# Sheet1.net
KiCad netlist of a schematic drawn in Altium Designer
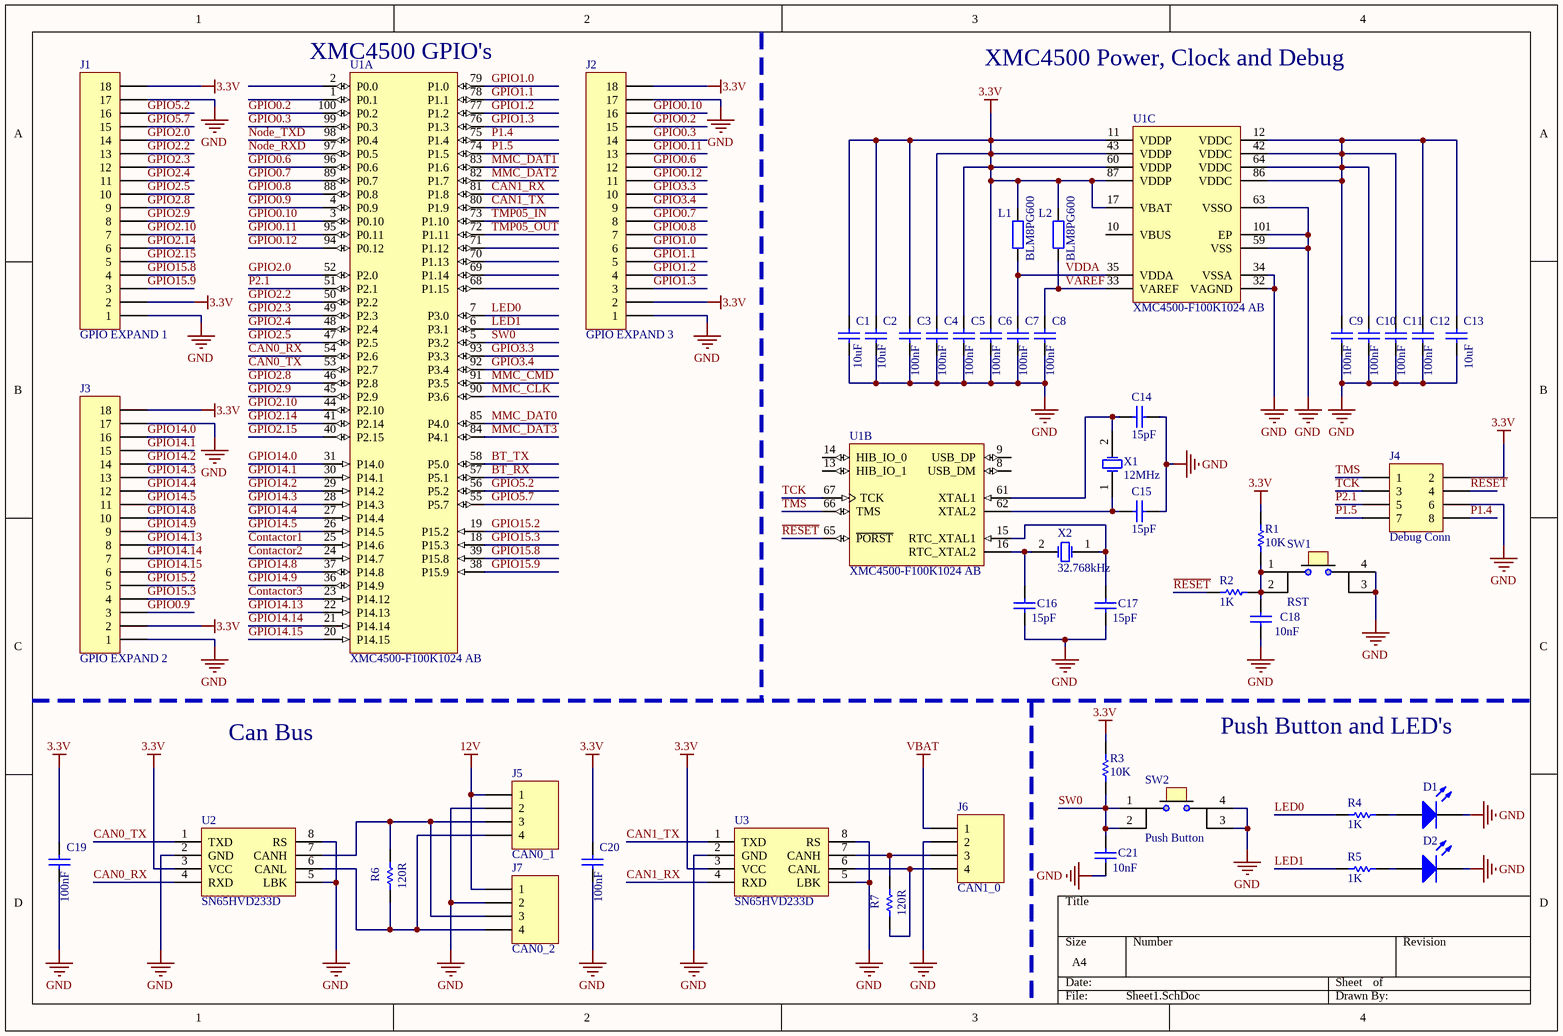
[diagram p0: Sheet1.SchDoc]

(export (version "E")
  (design (tool "Eeschema 10.0.6"))
  (components
    (comp (ref "C1")
      (value "10uF")
      (footprint "C0805")
      (fields (field (name "PUBLISHER") "Altium Limited"))
      (libsource (lib "Miscellaneous Devices") (part "Cap Semi"))
    )
    (comp (ref "C2")
      (value "10uF")
      (footprint "C0805")
      (fields (field (name "PUBLISHER") "Altium Limited"))
      (libsource (lib "Miscellaneous Devices") (part "Cap Semi"))
    )
    (comp (ref "C3")
      (value "100nF")
      (footprint "1608[0603]")
      (fields (field (name "PUBLISHER") "Altium Limited"))
      (libsource (lib "Miscellaneous Devices") (part "Cap Semi"))
    )
    (comp (ref "C4")
      (value "100nF")
      (footprint "1608[0603]")
      (fields (field (name "PUBLISHER") "Altium Limited"))
      (libsource (lib "Miscellaneous Devices") (part "Cap Semi"))
    )
    (comp (ref "C5")
      (value "100nF")
      (footprint "1608[0603]")
      (fields (field (name "PUBLISHER") "Altium Limited"))
      (libsource (lib "Miscellaneous Devices") (part "Cap Semi"))
    )
    (comp (ref "C6")
      (value "100nF")
      (footprint "1608[0603]")
      (fields (field (name "PUBLISHER") "Altium Limited"))
      (libsource (lib "Miscellaneous Devices") (part "Cap Semi"))
    )
    (comp (ref "C7")
      (value "100nF")
      (footprint "1608[0603]")
      (fields (field (name "PUBLISHER") "Altium Limited"))
      (libsource (lib "Miscellaneous Devices") (part "Cap Semi"))
    )
    (comp (ref "C8")
      (value "100nF")
      (footprint "1608[0603]")
      (fields (field (name "PUBLISHER") "Altium Limited"))
      (libsource (lib "Miscellaneous Devices") (part "Cap Semi"))
    )
    (comp (ref "C9")
      (value "100nF")
      (footprint "1608[0603]")
      (fields (field (name "PUBLISHER") "Altium Limited"))
      (libsource (lib "Miscellaneous Devices") (part "Cap Semi"))
    )
    (comp (ref "C10")
      (value "100nF")
      (footprint "1608[0603]")
      (fields (field (name "PUBLISHER") "Altium Limited"))
      (libsource (lib "Miscellaneous Devices") (part "Cap Semi"))
    )
    (comp (ref "C11")
      (value "100nF")
      (footprint "1608[0603]")
      (fields (field (name "PUBLISHER") "Altium Limited"))
      (libsource (lib "Miscellaneous Devices") (part "Cap Semi"))
    )
    (comp (ref "C12")
      (value "100nF")
      (footprint "1608[0603]")
      (fields (field (name "PUBLISHER") "Altium Limited"))
      (libsource (lib "Miscellaneous Devices") (part "Cap Semi"))
    )
    (comp (ref "C13")
      (value "10uF")
      (footprint "C0805")
      (fields (field (name "PUBLISHER") "Altium Limited"))
      (libsource (lib "Miscellaneous Devices") (part "Cap Semi"))
    )
    (comp (ref "C14")
      (value "15pF")
      (footprint "1608[0603]")
      (fields (field (name "PUBLISHER") "Altium Limited"))
      (libsource (lib "Miscellaneous Devices") (part "Cap Semi"))
    )
    (comp (ref "C15")
      (value "15pF")
      (footprint "1608[0603]")
      (fields (field (name "PUBLISHER") "Altium Limited"))
      (libsource (lib "Miscellaneous Devices") (part "Cap Semi"))
    )
    (comp (ref "C16")
      (value "15pF")
      (footprint "1608[0603]")
      (fields (field (name "PUBLISHER") "Altium Limited"))
      (libsource (lib "Miscellaneous Devices") (part "Cap Semi"))
    )
    (comp (ref "C17")
      (value "15pF")
      (footprint "1608[0603]")
      (fields (field (name "PUBLISHER") "Altium Limited"))
      (libsource (lib "Miscellaneous Devices") (part "Cap Semi"))
    )
    (comp (ref "C18")
      (value "10nF")
      (footprint "1608[0603]")
      (fields (field (name "PUBLISHER") "Altium Limited"))
      (libsource (lib "Miscellaneous Devices") (part "Cap Semi"))
    )
    (comp (ref "C19")
      (value "100nF")
      (footprint "1608[0603]")
      (fields (field (name "PUBLISHER") "Altium Limited"))
      (libsource (lib "Miscellaneous Devices") (part "Cap Semi"))
    )
    (comp (ref "C20")
      (value "100nF")
      (footprint "1608[0603]")
      (fields (field (name "PUBLISHER") "Altium Limited"))
      (libsource (lib "Miscellaneous Devices") (part "Cap Semi"))
    )
    (comp (ref "C21")
      (value "10nF")
      (footprint "1608[0603]")
      (fields (field (name "PUBLISHER") "Altium Limited"))
      (libsource (lib "Miscellaneous Devices") (part "Cap Semi"))
    )
    (comp (ref "D1")
      (value "SMD LED")
      (footprint "C0805")
      (fields (field (name "PUBLISHER") "Altium Limited"))
      (libsource (lib "Miscellaneous Devices") (part "LED0"))
    )
    (comp (ref "D2")
      (value "SMD LED")
      (footprint "C0805")
      (fields (field (name "PUBLISHER") "Altium Limited"))
      (libsource (lib "Miscellaneous Devices") (part "LED0"))
    )
    (comp (ref "J1")
      (value "GPIO EXPAND 1")
      (footprint "HDR1X18")
      (description "Header, 18-Pin")
      (fields (field (name "PUBLISHER") "Altium Limited"))
      (libsource (lib "Miscellaneous Connectors") (part "MHDR1X18"))
    )
    (comp (ref "J2")
      (value "GPIO EXPAND 3")
      (footprint "HDR1X18")
      (description "Header, 18-Pin")
      (fields (field (name "PUBLISHER") "Altium Limited"))
      (libsource (lib "Miscellaneous Connectors") (part "MHDR1X18"))
    )
    (comp (ref "J3")
      (value "GPIO EXPAND 2")
      (footprint "HDR1X18")
      (description "Header, 18-Pin")
      (fields (field (name "PUBLISHER") "Altium Limited"))
      (libsource (lib "Miscellaneous Connectors") (part "MHDR1X18"))
    )
    (comp (ref "J4")
      (value "Debug Conn")
      (footprint "HDR2X4")
      (description "Header, 4-Pin, Dual row")
      (fields (field (name "PUBLISHER") "Altium Limited"))
      (libsource (lib "Miscellaneous Connectors") (part "MHDR2X4"))
    )
    (comp (ref "J5")
      (value "CAN0_1")
      (footprint "4 Pin header")
      (description "4 pin header for CAN bus connectors")
      (libsource (lib "BMS") (part "4 Pin Vertical Header"))
    )
    (comp (ref "J6")
      (value "CAN1_0")
      (footprint "4 Pin header")
      (description "4 pin header for CAN bus connectors")
      (libsource (lib "BMS") (part "4 Pin Vertical Header"))
    )
    (comp (ref "J7")
      (value "CAN0_2")
      (footprint "4 Pin header")
      (description "4 pin header for CAN bus connectors")
      (libsource (lib "BMS") (part "4 Pin Vertical Header"))
    )
    (comp (ref "L1")
      (value "BLM8PG600")
      (footprint "C0805")
      (fields (field (name "PUBLISHER") "Altium Limited"))
      (libsource (lib "Miscellaneous Devices") (part "Res2"))
    )
    (comp (ref "L2")
      (value "BLM8PG600")
      (footprint "C0805")
      (fields (field (name "PUBLISHER") "Altium Limited"))
      (libsource (lib "Miscellaneous Devices") (part "Res2"))
    )
    (comp (ref "R1")
      (value "10K")
      (footprint "1608[0603]")
      (fields (field (name "PUBLISHER") "Altium Limited"))
      (libsource (lib "Miscellaneous Devices") (part "Res1"))
    )
    (comp (ref "R2")
      (value "1K")
      (footprint "1608[0603]")
      (description "10K")
      (fields (field (name "PUBLISHER") "Altium Limited"))
      (libsource (lib "Miscellaneous Devices") (part "Res1"))
    )
    (comp (ref "R3")
      (value "10K")
      (footprint "1608[0603]")
      (fields (field (name "PUBLISHER") "Altium Limited"))
      (libsource (lib "Miscellaneous Devices") (part "Res1"))
    )
    (comp (ref "R4")
      (value "1K")
      (footprint "1608[0603]")
      (fields (field (name "PUBLISHER") "Altium Limited"))
      (libsource (lib "Miscellaneous Devices") (part "Res1"))
    )
    (comp (ref "R5")
      (value "1K")
      (footprint "1608[0603]")
      (fields (field (name "PUBLISHER") "Altium Limited"))
      (libsource (lib "Miscellaneous Devices") (part "Res1"))
    )
    (comp (ref "R6")
      (value "120R")
      (footprint "C0805")
      (fields (field (name "PUBLISHER") "Altium Limited"))
      (libsource (lib "Miscellaneous Devices") (part "Res1"))
    )
    (comp (ref "R7")
      (value "120R")
      (footprint "C0805")
      (fields (field (name "PUBLISHER") "Altium Limited"))
      (libsource (lib "Miscellaneous Devices") (part "Res1"))
    )
    (comp (ref "SW1")
      (value "RST")
      (footprint "Push Button SMD")
      (description "General purposes push button")
      (libsource (lib "BMS") (part "Push Button"))
    )
    (comp (ref "SW2")
      (value "Push Button")
      (footprint "Push Button SMD")
      (description "General purposes push button")
      (libsource (lib "BMS") (part "Push Button"))
    )
    (comp (ref "U1")
      (value "XMC4500-F100K1024 AB")
      (footprint "INF-PG-LQFP-100-11-7000X7000TP_N")
      (fields (field (name "MANUFACTURER") "Infineon"))
      (libsource (lib "Infineon XMC4000") (part "XMC4500-F100K1024 AB"))
    )
    (comp (ref "U2")
      (value "SN65HVD233D")
      (footprint "SOIC 8")
      (description "SN65HVD233D 3.3V Can Tranceiver")
      (libsource (lib "BMS") (part "SN65HVD233D"))
    )
    (comp (ref "U3")
      (value "SN65HVD233D")
      (footprint "SOIC 8")
      (description "SN65HVD233D 3.3V Can Tranceiver")
      (libsource (lib "BMS") (part "SN65HVD233D"))
    )
    (comp (ref "X1")
      (value "12MHz")
      (footprint "SMD Crystall 23.2x2.5mm")
      (description "General purposes crystall symbol")
      (libsource (lib "BMS") (part "Crystall"))
    )
    (comp (ref "X2")
      (value "32.768kHz")
      (footprint "32kHz smd Crystal")
      (description "General purposes crystall symbol")
      (libsource (lib "BMS") (part "Crystall"))
    )
  )
  (nets
    (net (code "1") (name "/BT_RX") (class "Default")
      (node (ref "U1") (pin "57") (pinfunction "P5.1_57") (pintype "bidirectional"))
    )
    (net (code "2") (name "/BT_TX") (class "Default")
      (node (ref "U1") (pin "58") (pinfunction "P5.0_58") (pintype "bidirectional"))
    )
    (net (code "3") (name "/CAN0_RX") (class "Default")
      (node (ref "U1") (pin "54") (pinfunction "P2.6_54") (pintype "bidirectional"))
      (node (ref "U2") (pin "4") (pinfunction "RXD_4") (pintype "passive"))
    )
    (net (code "4") (name "/CAN0_TX") (class "Default")
      (node (ref "U1") (pin "53") (pinfunction "P2.7_53") (pintype "bidirectional"))
      (node (ref "U2") (pin "1") (pinfunction "TXD_1") (pintype "passive"))
    )
    (net (code "5") (name "/CAN1_RX") (class "Default")
      (node (ref "U1") (pin "81") (pinfunction "P1.8_81") (pintype "bidirectional"))
      (node (ref "U3") (pin "4") (pinfunction "RXD_4") (pintype "passive"))
    )
    (net (code "6") (name "/CAN1_TX") (class "Default")
      (node (ref "U1") (pin "80") (pinfunction "P1.9_80") (pintype "bidirectional"))
      (node (ref "U3") (pin "1") (pinfunction "TXD_1") (pintype "passive"))
    )
    (net (code "7") (name "/Contactor1") (class "Default")
      (node (ref "U1") (pin "25") (pinfunction "P14.6_25") (pintype "input"))
    )
    (net (code "8") (name "/Contactor2") (class "Default")
      (node (ref "U1") (pin "24") (pinfunction "P14.7_24") (pintype "input"))
    )
    (net (code "9") (name "/Contactor3") (class "Default")
      (node (ref "U1") (pin "23") (pinfunction "P14.12_23") (pintype "input"))
    )
    (net (code "10") (name "/GPIO0.2") (class "Default")
      (node (ref "J2") (pin "15") (pinfunction "15_15") (pintype "passive"))
      (node (ref "U1") (pin "100") (pinfunction "P0.2_100") (pintype "bidirectional"))
    )
    (net (code "11") (name "/GPIO0.3") (class "Default")
      (node (ref "J2") (pin "14") (pinfunction "14_14") (pintype "passive"))
      (node (ref "U1") (pin "99") (pinfunction "P0.3_99") (pintype "bidirectional"))
    )
    (net (code "12") (name "/GPIO0.6") (class "Default")
      (node (ref "J2") (pin "12") (pinfunction "12_12") (pintype "passive"))
      (node (ref "U1") (pin "96") (pinfunction "P0.6_96") (pintype "bidirectional"))
    )
    (net (code "13") (name "/GPIO0.7") (class "Default")
      (node (ref "J2") (pin "8") (pinfunction "8_8") (pintype "passive"))
      (node (ref "U1") (pin "89") (pinfunction "P0.7_89") (pintype "bidirectional"))
    )
    (net (code "14") (name "/GPIO0.8") (class "Default")
      (node (ref "J2") (pin "7") (pinfunction "7_7") (pintype "passive"))
      (node (ref "U1") (pin "88") (pinfunction "P0.8_88") (pintype "bidirectional"))
    )
    (net (code "15") (name "/GPIO0.9") (class "Default")
      (node (ref "J3") (pin "3") (pinfunction "3_3") (pintype "passive"))
      (node (ref "U1") (pin "4") (pinfunction "P0.9_4") (pintype "bidirectional"))
    )
    (net (code "16") (name "/GPIO0.10") (class "Default")
      (node (ref "J2") (pin "16") (pinfunction "16_16") (pintype "passive"))
      (node (ref "U1") (pin "3") (pinfunction "P0.10_3") (pintype "bidirectional"))
    )
    (net (code "17") (name "/GPIO0.11") (class "Default")
      (node (ref "J2") (pin "13") (pinfunction "13_13") (pintype "passive"))
      (node (ref "U1") (pin "95") (pinfunction "P0.11_95") (pintype "bidirectional"))
    )
    (net (code "18") (name "/GPIO0.12") (class "Default")
      (node (ref "J2") (pin "11") (pinfunction "11_11") (pintype "passive"))
      (node (ref "U1") (pin "94") (pinfunction "P0.12_94") (pintype "bidirectional"))
    )
    (net (code "19") (name "/GPIO1.0") (class "Default")
      (node (ref "J2") (pin "6") (pinfunction "6_6") (pintype "passive"))
      (node (ref "U1") (pin "79") (pinfunction "P1.0_79") (pintype "bidirectional"))
    )
    (net (code "20") (name "/GPIO1.1") (class "Default")
      (node (ref "J2") (pin "5") (pinfunction "5_5") (pintype "passive"))
      (node (ref "U1") (pin "78") (pinfunction "P1.1_78") (pintype "bidirectional"))
    )
    (net (code "21") (name "/GPIO1.2") (class "Default")
      (node (ref "J2") (pin "4") (pinfunction "4_4") (pintype "passive"))
      (node (ref "U1") (pin "77") (pinfunction "P1.2_77") (pintype "bidirectional"))
    )
    (net (code "22") (name "/GPIO1.3") (class "Default")
      (node (ref "J2") (pin "3") (pinfunction "3_3") (pintype "passive"))
      (node (ref "U1") (pin "76") (pinfunction "P1.3_76") (pintype "bidirectional"))
    )
    (net (code "23") (name "/GPIO2.0") (class "Default")
      (node (ref "J1") (pin "14") (pinfunction "14_14") (pintype "passive"))
      (node (ref "U1") (pin "52") (pinfunction "P2.0_52") (pintype "bidirectional"))
    )
    (net (code "24") (name "/GPIO2.2") (class "Default")
      (node (ref "J1") (pin "13") (pinfunction "13_13") (pintype "passive"))
      (node (ref "U1") (pin "50") (pinfunction "P2.2_50") (pintype "bidirectional"))
    )
    (net (code "25") (name "/GPIO2.3") (class "Default")
      (node (ref "J1") (pin "12") (pinfunction "12_12") (pintype "passive"))
      (node (ref "U1") (pin "49") (pinfunction "P2.3_49") (pintype "bidirectional"))
    )
    (net (code "26") (name "/GPIO2.4") (class "Default")
      (node (ref "J1") (pin "11") (pinfunction "11_11") (pintype "passive"))
      (node (ref "U1") (pin "48") (pinfunction "P2.4_48") (pintype "bidirectional"))
    )
    (net (code "27") (name "/GPIO2.5") (class "Default")
      (node (ref "J1") (pin "10") (pinfunction "10_10") (pintype "passive"))
      (node (ref "U1") (pin "47") (pinfunction "P2.5_47") (pintype "bidirectional"))
    )
    (net (code "28") (name "/GPIO2.8") (class "Default")
      (node (ref "J1") (pin "9") (pinfunction "9_9") (pintype "passive"))
      (node (ref "U1") (pin "46") (pinfunction "P2.8_46") (pintype "bidirectional"))
    )
    (net (code "29") (name "/GPIO2.9") (class "Default")
      (node (ref "J1") (pin "8") (pinfunction "8_8") (pintype "passive"))
      (node (ref "U1") (pin "45") (pinfunction "P2.9_45") (pintype "bidirectional"))
    )
    (net (code "30") (name "/GPIO2.10") (class "Default")
      (node (ref "J1") (pin "7") (pinfunction "7_7") (pintype "passive"))
      (node (ref "U1") (pin "44") (pinfunction "P2.10_44") (pintype "bidirectional"))
    )
    (net (code "31") (name "/GPIO2.14") (class "Default")
      (node (ref "J1") (pin "6") (pinfunction "6_6") (pintype "passive"))
      (node (ref "U1") (pin "41") (pinfunction "P2.14_41") (pintype "bidirectional"))
    )
    (net (code "32") (name "/GPIO2.15") (class "Default")
      (node (ref "J1") (pin "5") (pinfunction "5_5") (pintype "passive"))
      (node (ref "U1") (pin "40") (pinfunction "P2.15_40") (pintype "bidirectional"))
    )
    (net (code "33") (name "/GPIO3.3") (class "Default")
      (node (ref "J2") (pin "10") (pinfunction "10_10") (pintype "passive"))
      (node (ref "U1") (pin "93") (pinfunction "P3.3_93") (pintype "bidirectional"))
    )
    (net (code "34") (name "/GPIO3.4") (class "Default")
      (node (ref "J2") (pin "9") (pinfunction "9_9") (pintype "passive"))
      (node (ref "U1") (pin "92") (pinfunction "P3.4_92") (pintype "bidirectional"))
    )
    (net (code "35") (name "/GPIO5.2") (class "Default")
      (node (ref "J1") (pin "16") (pinfunction "16_16") (pintype "passive"))
      (node (ref "U1") (pin "56") (pinfunction "P5.2_56") (pintype "bidirectional"))
    )
    (net (code "36") (name "/GPIO5.7") (class "Default")
      (node (ref "J1") (pin "15") (pinfunction "15_15") (pintype "passive"))
      (node (ref "U1") (pin "55") (pinfunction "P5.7_55") (pintype "bidirectional"))
    )
    (net (code "37") (name "/GPIO14.0") (class "Default")
      (node (ref "J3") (pin "16") (pinfunction "16_16") (pintype "passive"))
      (node (ref "U1") (pin "31") (pinfunction "P14.0_31") (pintype "input"))
    )
    (net (code "38") (name "/GPIO14.1") (class "Default")
      (node (ref "J3") (pin "15") (pinfunction "15_15") (pintype "passive"))
      (node (ref "U1") (pin "30") (pinfunction "P14.1_30") (pintype "input"))
    )
    (net (code "39") (name "/GPIO14.2") (class "Default")
      (node (ref "J3") (pin "14") (pinfunction "14_14") (pintype "passive"))
      (node (ref "U1") (pin "29") (pinfunction "P14.2_29") (pintype "input"))
    )
    (net (code "40") (name "/GPIO14.3") (class "Default")
      (node (ref "J3") (pin "13") (pinfunction "13_13") (pintype "passive"))
      (node (ref "U1") (pin "28") (pinfunction "P14.3_28") (pintype "input"))
    )
    (net (code "41") (name "/GPIO14.4") (class "Default")
      (node (ref "J3") (pin "12") (pinfunction "12_12") (pintype "passive"))
      (node (ref "U1") (pin "27") (pinfunction "P14.4_27") (pintype "input"))
    )
    (net (code "42") (name "/GPIO14.5") (class "Default")
      (node (ref "J3") (pin "11") (pinfunction "11_11") (pintype "passive"))
      (node (ref "U1") (pin "26") (pinfunction "P14.5_26") (pintype "input"))
    )
    (net (code "43") (name "/GPIO14.8") (class "Default")
      (node (ref "J3") (pin "10") (pinfunction "10_10") (pintype "passive"))
      (node (ref "U1") (pin "37") (pinfunction "P14.8_37") (pintype "bidirectional"))
    )
    (net (code "44") (name "/GPIO14.9") (class "Default")
      (node (ref "J3") (pin "9") (pinfunction "9_9") (pintype "passive"))
      (node (ref "U1") (pin "36") (pinfunction "P14.9_36") (pintype "bidirectional"))
    )
    (net (code "45") (name "/GPIO14.13") (class "Default")
      (node (ref "J3") (pin "8") (pinfunction "8_8") (pintype "passive"))
      (node (ref "U1") (pin "22") (pinfunction "P14.13_22") (pintype "input"))
    )
    (net (code "46") (name "/GPIO14.14") (class "Default")
      (node (ref "J3") (pin "7") (pinfunction "7_7") (pintype "passive"))
      (node (ref "U1") (pin "21") (pinfunction "P14.14_21") (pintype "input"))
    )
    (net (code "47") (name "/GPIO14.15") (class "Default")
      (node (ref "J3") (pin "6") (pinfunction "6_6") (pintype "passive"))
      (node (ref "U1") (pin "20") (pinfunction "P14.15_20") (pintype "input"))
    )
    (net (code "48") (name "/GPIO15.2") (class "Default")
      (node (ref "J3") (pin "5") (pinfunction "5_5") (pintype "passive"))
      (node (ref "U1") (pin "19") (pinfunction "P15.2_19") (pintype "input"))
    )
    (net (code "49") (name "/GPIO15.3") (class "Default")
      (node (ref "J3") (pin "4") (pinfunction "4_4") (pintype "passive"))
      (node (ref "U1") (pin "18") (pinfunction "P15.3_18") (pintype "input"))
    )
    (net (code "50") (name "/GPIO15.8") (class "Default")
      (node (ref "J1") (pin "4") (pinfunction "4_4") (pintype "passive"))
      (node (ref "U1") (pin "39") (pinfunction "P15.8_39") (pintype "input"))
    )
    (net (code "51") (name "/GPIO15.9") (class "Default")
      (node (ref "J1") (pin "3") (pinfunction "3_3") (pintype "passive"))
      (node (ref "U1") (pin "38") (pinfunction "P15.9_38") (pintype "input"))
    )
    (net (code "52") (name "/LED0") (class "Default")
      (node (ref "R4") (pin "2") (pinfunction "2_2") (pintype "passive"))
      (node (ref "U1") (pin "7") (pinfunction "P3.0_7") (pintype "bidirectional"))
    )
    (net (code "53") (name "/LED1") (class "Default")
      (node (ref "R5") (pin "2") (pinfunction "2_2") (pintype "passive"))
      (node (ref "U1") (pin "6") (pinfunction "P3.1_6") (pintype "bidirectional"))
    )
    (net (code "54") (name "/MMC_CLK") (class "Default")
      (node (ref "U1") (pin "90") (pinfunction "P3.6_90") (pintype "bidirectional"))
    )
    (net (code "55") (name "/MMC_CMD") (class "Default")
      (node (ref "U1") (pin "91") (pinfunction "P3.5_91") (pintype "bidirectional"))
    )
    (net (code "56") (name "/MMC_DAT0") (class "Default")
      (node (ref "U1") (pin "85") (pinfunction "P4.0_85") (pintype "bidirectional"))
    )
    (net (code "57") (name "/MMC_DAT1") (class "Default")
      (node (ref "U1") (pin "83") (pinfunction "P1.6_83") (pintype "bidirectional"))
    )
    (net (code "58") (name "/MMC_DAT2") (class "Default")
      (node (ref "U1") (pin "82") (pinfunction "P1.7_82") (pintype "bidirectional"))
    )
    (net (code "59") (name "/MMC_DAT3") (class "Default")
      (node (ref "U1") (pin "84") (pinfunction "P4.1_84") (pintype "bidirectional"))
    )
    (net (code "60") (name "/Node_RXD") (class "Default")
      (node (ref "U1") (pin "97") (pinfunction "P0.5_97") (pintype "bidirectional"))
    )
    (net (code "61") (name "/Node_TXD") (class "Default")
      (node (ref "U1") (pin "98") (pinfunction "P0.4_98") (pintype "bidirectional"))
    )
    (net (code "62") (name "/P1.4") (class "Default")
      (node (ref "J4") (pin "8") (pinfunction "8_8") (pintype "passive"))
      (node (ref "U1") (pin "75") (pinfunction "P1.4_75") (pintype "bidirectional"))
    )
    (net (code "63") (name "/P1.5") (class "Default")
      (node (ref "J4") (pin "7") (pinfunction "7_7") (pintype "passive"))
      (node (ref "U1") (pin "74") (pinfunction "P1.5_74") (pintype "bidirectional"))
    )
    (net (code "64") (name "/P2.1") (class "Default")
      (node (ref "J4") (pin "5") (pinfunction "5_5") (pintype "passive"))
      (node (ref "U1") (pin "51") (pinfunction "P2.1_51") (pintype "bidirectional"))
    )
    (net (code "65") (name "/SW0") (class "Default")
      (node (ref "C21") (pin "2") (pinfunction "2_2") (pintype "passive"))
      (node (ref "R3") (pin "2") (pinfunction "2_2") (pintype "passive"))
      (node (ref "SW2") (pin "1") (pinfunction "1_1") (pintype "passive"))
      (node (ref "SW2") (pin "2") (pinfunction "2_2") (pintype "passive"))
      (node (ref "U1") (pin "5") (pinfunction "P3.2_5") (pintype "bidirectional"))
    )
    (net (code "66") (name "/TCK") (class "Default")
      (node (ref "J4") (pin "3") (pinfunction "3_3") (pintype "passive"))
      (node (ref "U1") (pin "67") (pinfunction "TCK_67") (pintype "input"))
    )
    (net (code "67") (name "/TMP05_IN") (class "Default")
      (node (ref "U1") (pin "73") (pinfunction "P1.10_73") (pintype "bidirectional"))
    )
    (net (code "68") (name "/TMP05_OUT") (class "Default")
      (node (ref "U1") (pin "72") (pinfunction "P1.11_72") (pintype "bidirectional"))
    )
    (net (code "69") (name "/TMS") (class "Default")
      (node (ref "J4") (pin "1") (pinfunction "1_1") (pintype "passive"))
      (node (ref "U1") (pin "66") (pinfunction "TMS_66") (pintype "bidirectional"))
    )
    (net (code "70") (name "/VAREF") (class "Default")
      (node (ref "C8") (pin "2") (pinfunction "2_2") (pintype "passive"))
      (node (ref "L2") (pin "1") (pinfunction "1_1") (pintype "passive"))
      (node (ref "U1") (pin "33") (pinfunction "VAREF_33") (pintype "power_in"))
    )
    (net (code "71") (name "/VDDA") (class "Default")
      (node (ref "C7") (pin "2") (pinfunction "2_2") (pintype "passive"))
      (node (ref "L1") (pin "1") (pinfunction "1_1") (pintype "passive"))
      (node (ref "U1") (pin "35") (pinfunction "VDDA_35") (pintype "power_in"))
    )
    (net (code "72") (name "/~{RESET}") (class "Default")
      (node (ref "J4") (pin "4") (pinfunction "4_4") (pintype "passive"))
      (node (ref "R2") (pin "1") (pinfunction "1_1") (pintype "passive"))
      (node (ref "U1") (pin "65") (pinfunction "~{PORST}_65") (pintype "bidirectional"))
    )
    (net (code "73") (name "3.3V") (class "Default")
      (node (ref "C1") (pin "2") (pinfunction "2_2") (pintype "passive"))
      (node (ref "C19") (pin "2") (pinfunction "2_2") (pintype "passive"))
      (node (ref "C2") (pin "2") (pinfunction "2_2") (pintype "passive"))
      (node (ref "C20") (pin "2") (pinfunction "2_2") (pintype "passive"))
      (node (ref "C3") (pin "2") (pinfunction "2_2") (pintype "passive"))
      (node (ref "C4") (pin "2") (pinfunction "2_2") (pintype "passive"))
      (node (ref "C5") (pin "2") (pinfunction "2_2") (pintype "passive"))
      (node (ref "C6") (pin "2") (pinfunction "2_2") (pintype "passive"))
      (node (ref "J1") (pin "18") (pinfunction "18_18") (pintype "passive"))
      (node (ref "J1") (pin "2") (pinfunction "2_2") (pintype "passive"))
      (node (ref "J2") (pin "18") (pinfunction "18_18") (pintype "passive"))
      (node (ref "J2") (pin "2") (pinfunction "2_2") (pintype "passive"))
      (node (ref "J3") (pin "18") (pinfunction "18_18") (pintype "passive"))
      (node (ref "J3") (pin "2") (pinfunction "2_2") (pintype "passive"))
      (node (ref "J4") (pin "2") (pinfunction "2_2") (pintype "passive"))
      (node (ref "L1") (pin "2") (pinfunction "2_2") (pintype "passive"))
      (node (ref "L2") (pin "2") (pinfunction "2_2") (pintype "passive"))
      (node (ref "R1") (pin "1") (pinfunction "1_1") (pintype "passive"))
      (node (ref "R3") (pin "1") (pinfunction "1_1") (pintype "passive"))
      (node (ref "U1") (pin "11") (pinfunction "VDDP_11") (pintype "power_in"))
      (node (ref "U1") (pin "17") (pinfunction "VBAT_17") (pintype "power_in"))
      (node (ref "U1") (pin "43") (pinfunction "VDDP_43") (pintype "power_in"))
      (node (ref "U1") (pin "60") (pinfunction "VDDP_60") (pintype "power_in"))
      (node (ref "U1") (pin "87") (pinfunction "VDDP_87") (pintype "power_in"))
      (node (ref "U2") (pin "3") (pinfunction "VCC_3") (pintype "passive"))
      (node (ref "U3") (pin "3") (pinfunction "VCC_3") (pintype "passive"))
    )
    (net (code "74") (name "12V") (class "Default")
      (node (ref "J5") (pin "1") (pinfunction "1_1") (pintype "passive"))
      (node (ref "J7") (pin "1") (pinfunction "1_1") (pintype "passive"))
    )
    (net (code "75") (name "GND") (class "Default")
      (node (ref "C1") (pin "1") (pinfunction "1_1") (pintype "passive"))
      (node (ref "C10") (pin "1") (pinfunction "1_1") (pintype "passive"))
      (node (ref "C11") (pin "1") (pinfunction "1_1") (pintype "passive"))
      (node (ref "C12") (pin "1") (pinfunction "1_1") (pintype "passive"))
      (node (ref "C13") (pin "1") (pinfunction "1_1") (pintype "passive"))
      (node (ref "C14") (pin "1") (pinfunction "1_1") (pintype "passive"))
      (node (ref "C15") (pin "1") (pinfunction "1_1") (pintype "passive"))
      (node (ref "C16") (pin "1") (pinfunction "1_1") (pintype "passive"))
      (node (ref "C17") (pin "1") (pinfunction "1_1") (pintype "passive"))
      (node (ref "C18") (pin "1") (pinfunction "1_1") (pintype "passive"))
      (node (ref "C19") (pin "1") (pinfunction "1_1") (pintype "passive"))
      (node (ref "C2") (pin "1") (pinfunction "1_1") (pintype "passive"))
      (node (ref "C20") (pin "1") (pinfunction "1_1") (pintype "passive"))
      (node (ref "C21") (pin "1") (pinfunction "1_1") (pintype "passive"))
      (node (ref "C3") (pin "1") (pinfunction "1_1") (pintype "passive"))
      (node (ref "C4") (pin "1") (pinfunction "1_1") (pintype "passive"))
      (node (ref "C5") (pin "1") (pinfunction "1_1") (pintype "passive"))
      (node (ref "C6") (pin "1") (pinfunction "1_1") (pintype "passive"))
      (node (ref "C7") (pin "1") (pinfunction "1_1") (pintype "passive"))
      (node (ref "C8") (pin "1") (pinfunction "1_1") (pintype "passive"))
      (node (ref "C9") (pin "1") (pinfunction "1_1") (pintype "passive"))
      (node (ref "D1") (pin "2") (pinfunction "K_2") (pintype "passive"))
      (node (ref "D2") (pin "2") (pinfunction "K_2") (pintype "passive"))
      (node (ref "J1") (pin "1") (pinfunction "1_1") (pintype "passive"))
      (node (ref "J1") (pin "17") (pinfunction "17_17") (pintype "passive"))
      (node (ref "J2") (pin "1") (pinfunction "1_1") (pintype "passive"))
      (node (ref "J2") (pin "17") (pinfunction "17_17") (pintype "passive"))
      (node (ref "J3") (pin "1") (pinfunction "1_1") (pintype "passive"))
      (node (ref "J3") (pin "17") (pinfunction "17_17") (pintype "passive"))
      (node (ref "J4") (pin "6") (pinfunction "6_6") (pintype "passive"))
      (node (ref "J5") (pin "2") (pinfunction "2_2") (pintype "passive"))
      (node (ref "J6") (pin "2") (pinfunction "2_2") (pintype "passive"))
      (node (ref "J7") (pin "2") (pinfunction "2_2") (pintype "passive"))
      (node (ref "SW1") (pin "3") (pinfunction "3_3") (pintype "passive"))
      (node (ref "SW1") (pin "4") (pinfunction "4_4") (pintype "passive"))
      (node (ref "SW2") (pin "3") (pinfunction "3_3") (pintype "passive"))
      (node (ref "SW2") (pin "4") (pinfunction "4_4") (pintype "passive"))
      (node (ref "U1") (pin "101") (pinfunction "EP_101") (pintype "power_in"))
      (node (ref "U1") (pin "32") (pinfunction "VAGND_32") (pintype "power_in"))
      (node (ref "U1") (pin "34") (pinfunction "VSSA_34") (pintype "power_in"))
      (node (ref "U1") (pin "59") (pinfunction "VSS_59") (pintype "power_in"))
      (node (ref "U1") (pin "63") (pinfunction "VSSO_63") (pintype "power_in"))
      (node (ref "U2") (pin "2") (pinfunction "GND_2") (pintype "passive"))
      (node (ref "U2") (pin "5") (pinfunction "LBK_5") (pintype "passive"))
      (node (ref "U2") (pin "8") (pinfunction "RS_8") (pintype "passive"))
      (node (ref "U3") (pin "2") (pinfunction "GND_2") (pintype "passive"))
      (node (ref "U3") (pin "5") (pinfunction "LBK_5") (pintype "passive"))
      (node (ref "U3") (pin "8") (pinfunction "RS_8") (pintype "passive"))
    )
    (net (code "76") (name "Net-(C10-Pad2)") (class "Default")
      (node (ref "C10") (pin "2") (pinfunction "2_2") (pintype "passive"))
      (node (ref "C11") (pin "2") (pinfunction "2_2") (pintype "passive"))
      (node (ref "C12") (pin "2") (pinfunction "2_2") (pintype "passive"))
      (node (ref "C13") (pin "2") (pinfunction "2_2") (pintype "passive"))
      (node (ref "C9") (pin "2") (pinfunction "2_2") (pintype "passive"))
      (node (ref "U1") (pin "12") (pinfunction "VDDC_12") (pintype "power_in"))
      (node (ref "U1") (pin "42") (pinfunction "VDDC_42") (pintype "power_in"))
      (node (ref "U1") (pin "64") (pinfunction "VDDC_64") (pintype "power_in"))
      (node (ref "U1") (pin "86") (pinfunction "VDDC_86") (pintype "power_in"))
    )
    (net (code "77") (name "Net-(C18-Pad2)") (class "Default")
      (node (ref "C18") (pin "2") (pinfunction "2_2") (pintype "passive"))
      (node (ref "R1") (pin "2") (pinfunction "2_2") (pintype "passive"))
      (node (ref "R2") (pin "2") (pinfunction "2_2") (pintype "passive"))
      (node (ref "SW1") (pin "1") (pinfunction "1_1") (pintype "passive"))
      (node (ref "SW1") (pin "2") (pinfunction "2_2") (pintype "passive"))
    )
    (net (code "78") (name "Net-(D1-A)") (class "Default")
      (node (ref "D1") (pin "1") (pinfunction "A_1") (pintype "passive"))
      (node (ref "R4") (pin "1") (pinfunction "1_1") (pintype "passive"))
    )
    (net (code "79") (name "Net-(D2-A)") (class "Default")
      (node (ref "D2") (pin "1") (pinfunction "A_1") (pintype "passive"))
      (node (ref "R5") (pin "1") (pinfunction "1_1") (pintype "passive"))
    )
    (net (code "80") (name "Net-(U1B-RTC_XTAL1)") (class "Default")
      (node (ref "C17") (pin "2") (pinfunction "2_2") (pintype "passive"))
      (node (ref "U1") (pin "15") (pinfunction "RTC_XTAL1_15") (pintype "input"))
      (node (ref "X2") (pin "1") (pinfunction "OSC1_1") (pintype "passive"))
    )
    (net (code "81") (name "Net-(U1B-RTC_XTAL2)") (class "Default")
      (node (ref "C16") (pin "2") (pinfunction "2_2") (pintype "passive"))
      (node (ref "U1") (pin "16") (pinfunction "RTC_XTAL2_16") (pintype "passive"))
      (node (ref "X2") (pin "2") (pinfunction "OSC2_2") (pintype "passive"))
    )
    (net (code "82") (name "Net-(U1B-XTAL1)") (class "Default")
      (node (ref "C14") (pin "2") (pinfunction "2_2") (pintype "passive"))
      (node (ref "U1") (pin "61") (pinfunction "XTAL1_61") (pintype "input"))
      (node (ref "X1") (pin "2") (pinfunction "OSC2_2") (pintype "passive"))
    )
    (net (code "83") (name "Net-(U1B-XTAL2)") (class "Default")
      (node (ref "C15") (pin "2") (pinfunction "2_2") (pintype "passive"))
      (node (ref "U1") (pin "62") (pinfunction "XTAL2_62") (pintype "passive"))
      (node (ref "X1") (pin "1") (pinfunction "OSC1_1") (pintype "passive"))
    )
    (net (code "84") (name "Net-(U2-CANH)") (class "Default")
      (node (ref "J5") (pin "3") (pinfunction "3_3") (pintype "passive"))
      (node (ref "J7") (pin "3") (pinfunction "3_3") (pintype "passive"))
      (node (ref "R6") (pin "2") (pinfunction "2_2") (pintype "passive"))
      (node (ref "U2") (pin "7") (pinfunction "CANH_7") (pintype "passive"))
    )
    (net (code "85") (name "Net-(U2-CANL)") (class "Default")
      (node (ref "J5") (pin "4") (pinfunction "4_4") (pintype "passive"))
      (node (ref "J7") (pin "4") (pinfunction "4_4") (pintype "passive"))
      (node (ref "R6") (pin "1") (pinfunction "1_1") (pintype "passive"))
      (node (ref "U2") (pin "6") (pinfunction "CANL_6") (pintype "passive"))
    )
    (net (code "86") (name "Net-(U3-CANH)") (class "Default")
      (node (ref "J6") (pin "3") (pinfunction "3_3") (pintype "passive"))
      (node (ref "R7") (pin "2") (pinfunction "2_2") (pintype "passive"))
      (node (ref "U3") (pin "7") (pinfunction "CANH_7") (pintype "passive"))
    )
    (net (code "87") (name "Net-(U3-CANL)") (class "Default")
      (node (ref "J6") (pin "4") (pinfunction "4_4") (pintype "passive"))
      (node (ref "R7") (pin "1") (pinfunction "1_1") (pintype "passive"))
      (node (ref "U3") (pin "6") (pinfunction "CANL_6") (pintype "passive"))
    )
    (net (code "88") (name "VBAT") (class "Default")
      (node (ref "J6") (pin "1") (pinfunction "1_1") (pintype "passive"))
    )
    (net (code "89") (name "unconnected-(U1A-P0.0-Pad2)") (class "Default")
      (node (ref "U1") (pin "2") (pinfunction "P0.0_2") (pintype "bidirectional"))
    )
    (net (code "90") (name "unconnected-(U1A-P0.1-Pad1)") (class "Default")
      (node (ref "U1") (pin "1") (pinfunction "P0.1_1") (pintype "bidirectional"))
    )
    (net (code "91") (name "unconnected-(U1A-P1.12-Pad71)") (class "Default")
      (node (ref "U1") (pin "71") (pinfunction "P1.12_71") (pintype "bidirectional"))
    )
    (net (code "92") (name "unconnected-(U1A-P1.13-Pad70)") (class "Default")
      (node (ref "U1") (pin "70") (pinfunction "P1.13_70") (pintype "bidirectional"))
    )
    (net (code "93") (name "unconnected-(U1A-P1.14-Pad69)") (class "Default")
      (node (ref "U1") (pin "69") (pinfunction "P1.14_69") (pintype "bidirectional"))
    )
    (net (code "94") (name "unconnected-(U1A-P1.15-Pad68)") (class "Default")
      (node (ref "U1") (pin "68") (pinfunction "P1.15_68") (pintype "bidirectional"))
    )
    (net (code "95") (name "unconnected-(U1B-HIB_IO_0-Pad14)") (class "Default")
      (node (ref "U1") (pin "14") (pinfunction "HIB_IO_0_14") (pintype "bidirectional"))
    )
    (net (code "96") (name "unconnected-(U1B-HIB_IO_1-Pad13)") (class "Default")
      (node (ref "U1") (pin "13") (pinfunction "HIB_IO_1_13") (pintype "bidirectional"))
    )
    (net (code "97") (name "unconnected-(U1B-USB_DM-Pad8)") (class "Default")
      (node (ref "U1") (pin "8") (pinfunction "USB_DM_8") (pintype "bidirectional"))
    )
    (net (code "98") (name "unconnected-(U1B-USB_DP-Pad9)") (class "Default")
      (node (ref "U1") (pin "9") (pinfunction "USB_DP_9") (pintype "bidirectional"))
    )
    (net (code "99") (name "unconnected-(U1C-VBUS-Pad10)") (class "Default")
      (node (ref "U1") (pin "10") (pinfunction "VBUS_10") (pintype "power_in"))
    )
  )
)
